# host.net
KiCad netlist of a schematic drawn in EAGLE
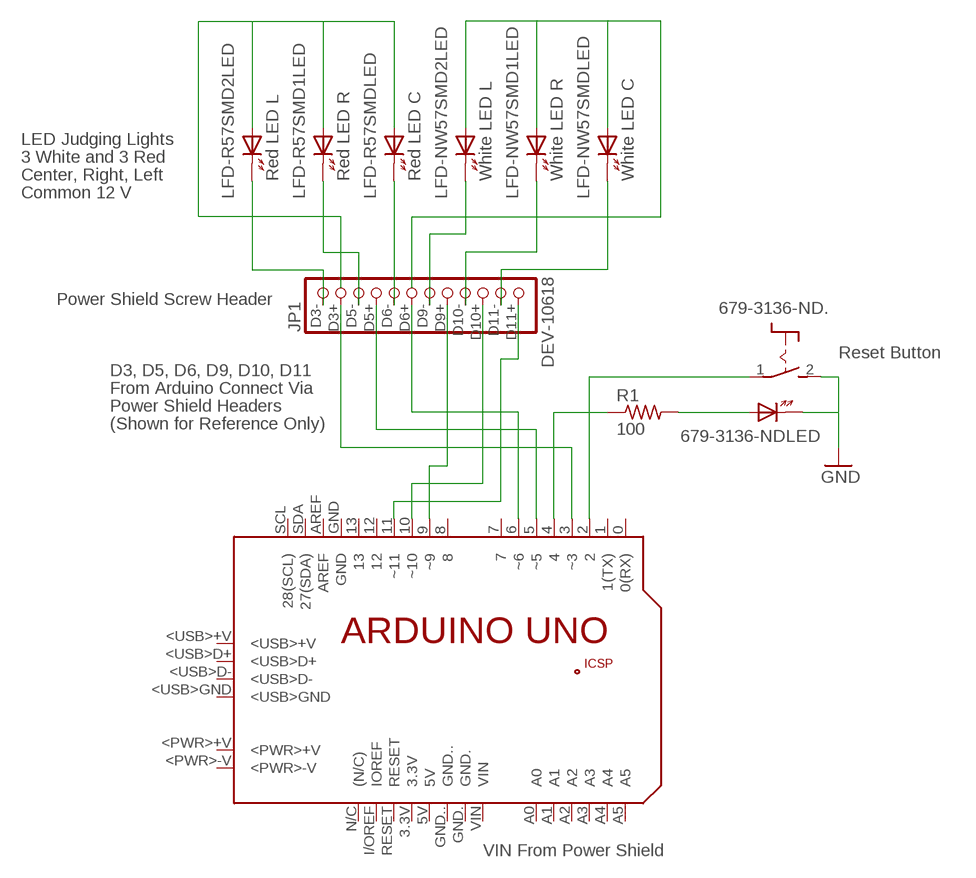
[diagram p0: schematic, sheet 1]

(export (version "E")
  (design (tool "Eeschema 10.0.6"))
  (components
    (comp (ref "679-3136-ND")
      (value "MARQ6425")
      (footprint "eagle-import:MARQ6425")
      (libsource (lib "eagle-import") (part "MARQ6425"))
    )
    (comp (ref "JP1")
      (value "DEV-10618")
      (footprint "eagle-import:1X12")
      (libsource (lib "eagle-import") (part "PINHD-1X12"))
    )
    (comp (ref "LFD-NW57SMD")
      (value "White LED C")
      (footprint "eagle-import:MARQ6425")
      (libsource (lib "eagle-import") (part "MARQ6425"))
    )
    (comp (ref "LFD-NW57SMD1")
      (value "White LED R")
      (footprint "eagle-import:MARQ6425")
      (libsource (lib "eagle-import") (part "MARQ6425"))
    )
    (comp (ref "LFD-NW57SMD2")
      (value "White LED L")
      (footprint "eagle-import:MARQ6425")
      (libsource (lib "eagle-import") (part "MARQ6425"))
    )
    (comp (ref "LFD-R57SMD")
      (value "Red LED C")
      (footprint "eagle-import:MARQ6425")
      (libsource (lib "eagle-import") (part "MARQ6425"))
    )
    (comp (ref "LFD-R57SMD1")
      (value "Red LED R")
      (footprint "eagle-import:MARQ6425")
      (libsource (lib "eagle-import") (part "MARQ6425"))
    )
    (comp (ref "LFD-R57SMD2")
      (value "Red LED L")
      (footprint "eagle-import:MARQ6425")
      (libsource (lib "eagle-import") (part "MARQ6425"))
    )
    (comp (ref "PCB1")
      (value "ARDUINO_UNO")
      (footprint "eagle-import:ARDUINO_UNO")
      (libsource (lib "eagle-import") (part "ARDUINO_UNO"))
    )
    (comp (ref "R1")
      (value "100")
      (footprint "eagle-import:0204V")
      (libsource (lib "eagle-import") (part "R-US_0204/2V"))
    )
  )
  (nets
    (net (code "1") (name "GND") (class "Default")
      (node (ref "679-3136-ND") (pin "2") (pinfunction "S_2") (pintype "passive"))
      (node (ref "679-3136-ND") (pin "K") (pinfunction "K_K") (pintype "passive"))
    )
    (net (code "2") (name "Net-(679-3136-ND-PadA)") (class "Default")
      (node (ref "679-3136-ND") (pin "A") (pinfunction "A_A") (pintype "passive"))
      (node (ref "R1") (pin "2") (pinfunction "2_2") (pintype "passive"))
    )
    (net (code "3") (name "Net-(679-3136-NDA-P)") (class "Default")
      (node (ref "679-3136-ND") (pin "1") (pinfunction "P_1") (pintype "passive"))
      (node (ref "PCB1") (pin "2") (pinfunction "2_2") (pintype "bidirectional"))
    )
    (net (code "4") (name "Net-(JP1-PadD3-)") (class "Default")
      (node (ref "JP1") (pin "D3-") (pinfunction "D3-_D3-") (pintype "passive"))
      (node (ref "LFD-R57SMD2") (pin "K") (pinfunction "K_K") (pintype "passive"))
    )
    (net (code "5") (name "Net-(JP1-PadD5-)") (class "Default")
      (node (ref "JP1") (pin "D5-") (pinfunction "D5-_D5-") (pintype "passive"))
      (node (ref "LFD-R57SMD1") (pin "K") (pinfunction "K_K") (pintype "passive"))
    )
    (net (code "6") (name "Net-(JP1-PadD6-)") (class "Default")
      (node (ref "JP1") (pin "D6-") (pinfunction "D6-_D6-") (pintype "passive"))
      (node (ref "LFD-R57SMD") (pin "K") (pinfunction "K_K") (pintype "passive"))
    )
    (net (code "7") (name "Net-(JP1-PadD9-)") (class "Default")
      (node (ref "JP1") (pin "D9-") (pinfunction "D9-_D9-") (pintype "passive"))
      (node (ref "LFD-NW57SMD2") (pin "K") (pinfunction "K_K") (pintype "passive"))
    )
    (net (code "8") (name "Net-(JP1-PadD10-)") (class "Default")
      (node (ref "JP1") (pin "D10-") (pinfunction "D10-_D10-") (pintype "passive"))
      (node (ref "LFD-NW57SMD1") (pin "K") (pinfunction "K_K") (pintype "passive"))
    )
    (net (code "9") (name "Net-(JP1-PadD11-)") (class "Default")
      (node (ref "JP1") (pin "D11-") (pinfunction "D11-_D11-") (pintype "passive"))
      (node (ref "LFD-NW57SMD") (pin "K") (pinfunction "K_K") (pintype "passive"))
    )
    (net (code "10") (name "Net-(LFD-NW57SMD-PadA)") (class "Default")
      (node (ref "LFD-NW57SMD") (pin "A") (pinfunction "A_A") (pintype "passive"))
      (node (ref "LFD-NW57SMD1") (pin "A") (pinfunction "A_A") (pintype "passive"))
      (node (ref "LFD-NW57SMD2") (pin "A") (pinfunction "A_A") (pintype "passive"))
    )
    (net (code "11") (name "Net-(LFD-R57SMD-PadA)") (class "Default")
      (node (ref "LFD-R57SMD") (pin "A") (pinfunction "A_A") (pintype "passive"))
      (node (ref "LFD-R57SMD1") (pin "A") (pinfunction "A_A") (pintype "passive"))
      (node (ref "LFD-R57SMD2") (pin "A") (pinfunction "A_A") (pintype "passive"))
    )
    (net (code "12") (name "Net-(PCB1-Pad4)") (class "Default")
      (node (ref "PCB1") (pin "4") (pinfunction "4_4") (pintype "bidirectional"))
      (node (ref "R1") (pin "1") (pinfunction "1_1") (pintype "passive"))
    )
    (net (code "13") (name "Net-(PCB1-~{3})") (class "Default")
      (node (ref "JP1") (pin "D3+") (pinfunction "D3+_D3+") (pintype "passive"))
      (node (ref "PCB1") (pin "3") (pinfunction "~{3}_3") (pintype "bidirectional"))
    )
    (net (code "14") (name "Net-(PCB1-~{5})") (class "Default")
      (node (ref "JP1") (pin "D5+") (pinfunction "D5+_D5+") (pintype "passive"))
      (node (ref "PCB1") (pin "5") (pinfunction "~{5}_5") (pintype "bidirectional"))
    )
    (net (code "15") (name "Net-(PCB1-~{6})") (class "Default")
      (node (ref "JP1") (pin "D6+") (pinfunction "D6+_D6+") (pintype "passive"))
      (node (ref "PCB1") (pin "6") (pinfunction "~{6}_6") (pintype "bidirectional"))
    )
    (net (code "16") (name "Net-(PCB1-~{9})") (class "Default")
      (node (ref "JP1") (pin "D9+") (pinfunction "D9+_D9+") (pintype "passive"))
      (node (ref "PCB1") (pin "9") (pinfunction "~{9}_9") (pintype "bidirectional"))
    )
    (net (code "17") (name "Net-(PCB1-~{10})") (class "Default")
      (node (ref "JP1") (pin "D10+") (pinfunction "D10+_D10+") (pintype "passive"))
      (node (ref "PCB1") (pin "10") (pinfunction "~{10}_10") (pintype "bidirectional"))
    )
    (net (code "18") (name "Net-(PCB1-~{11})") (class "Default")
      (node (ref "JP1") (pin "D11+") (pinfunction "D11+_D11+") (pintype "passive"))
      (node (ref "PCB1") (pin "11") (pinfunction "~{11}_11") (pintype "bidirectional"))
    )
    (net (code "19") (name "unconnected-(PCB1-(N{slash}C)-PadN{slash}C)") (class "Default")
      (node (ref "PCB1") (pin "N/C") (pinfunction "(N/C)_N/C") (pintype "bidirectional"))
    )
    (net (code "20") (name "unconnected-(PCB1-0(RX)-Pad0)") (class "Default")
      (node (ref "PCB1") (pin "0") (pinfunction "0(RX)_0") (pintype "bidirectional"))
    )
    (net (code "21") (name "unconnected-(PCB1-1(TX)-Pad1)") (class "Default")
      (node (ref "PCB1") (pin "1") (pinfunction "1(TX)_1") (pintype "bidirectional"))
    )
    (net (code "22") (name "unconnected-(PCB1-27(SDA)-PadSDA)") (class "Default")
      (node (ref "PCB1") (pin "SDA") (pinfunction "27(SDA)_SDA") (pintype "bidirectional"))
    )
    (net (code "23") (name "unconnected-(PCB1-28(SCL)-PadSCL)") (class "Default")
      (node (ref "PCB1") (pin "SCL") (pinfunction "28(SCL)_SCL") (pintype "bidirectional"))
    )
    (net (code "24") (name "unconnected-(PCB1-IOREF-PadI{slash}OREF)") (class "Default")
      (node (ref "PCB1") (pin "I/OREF") (pinfunction "IOREF_I/OREF") (pintype "bidirectional"))
    )
    (net (code "25") (name "unconnected-(PCB1-Pad+5V)") (class "Default")
      (node (ref "PCB1") (pin "+5V") (pinfunction "+5V_+5V") (pintype "bidirectional"))
    )
    (net (code "26") (name "unconnected-(PCB1-Pad3.3V)") (class "Default")
      (node (ref "PCB1") (pin "3.3V") (pinfunction "3.3V_3.3V") (pintype "bidirectional"))
    )
    (net (code "27") (name "unconnected-(PCB1-Pad5V)") (class "Default")
      (node (ref "PCB1") (pin "5V") (pinfunction "5V_5V") (pintype "bidirectional"))
    )
    (net (code "28") (name "unconnected-(PCB1-Pad7)") (class "Default")
      (node (ref "PCB1") (pin "7") (pinfunction "7_7") (pintype "bidirectional"))
    )
    (net (code "29") (name "unconnected-(PCB1-Pad8)") (class "Default")
      (node (ref "PCB1") (pin "8") (pinfunction "8_8") (pintype "bidirectional"))
    )
    (net (code "30") (name "unconnected-(PCB1-Pad12)") (class "Default")
      (node (ref "PCB1") (pin "12") (pinfunction "12_12") (pintype "bidirectional"))
    )
    (net (code "31") (name "unconnected-(PCB1-Pad13)") (class "Default")
      (node (ref "PCB1") (pin "13") (pinfunction "13_13") (pintype "bidirectional"))
    )
    (net (code "32") (name "unconnected-(PCB1-Pad<PWR>+V)") (class "Default")
      (node (ref "PCB1") (pin "<PWR>+V") (pinfunction "<PWR>+V_<PWR>+V") (pintype "bidirectional"))
    )
    (net (code "33") (name "unconnected-(PCB1-Pad<PWR>-V)") (class "Default")
      (node (ref "PCB1") (pin "<PWR>-V") (pinfunction "<PWR>-V_<PWR>-V") (pintype "bidirectional"))
    )
    (net (code "34") (name "unconnected-(PCB1-Pad<USB>+V)") (class "Default")
      (node (ref "PCB1") (pin "<USB>+V") (pinfunction "<USB>+V_<USB>+V") (pintype "bidirectional"))
    )
    (net (code "35") (name "unconnected-(PCB1-Pad<USB>D+)") (class "Default")
      (node (ref "PCB1") (pin "<USB>D+") (pinfunction "<USB>D+_<USB>D+") (pintype "bidirectional"))
    )
    (net (code "36") (name "unconnected-(PCB1-Pad<USB>D-)") (class "Default")
      (node (ref "PCB1") (pin "<USB>D-") (pinfunction "<USB>D-_<USB>D-") (pintype "bidirectional"))
    )
    (net (code "37") (name "unconnected-(PCB1-Pad<USB>GND)") (class "Default")
      (node (ref "PCB1") (pin "<USB>GND") (pinfunction "<USB>GND_<USB>GND") (pintype "bidirectional"))
    )
    (net (code "38") (name "unconnected-(PCB1-PadA0)") (class "Default")
      (node (ref "PCB1") (pin "A0") (pinfunction "A0_A0") (pintype "bidirectional"))
    )
    (net (code "39") (name "unconnected-(PCB1-PadA1)") (class "Default")
      (node (ref "PCB1") (pin "A1") (pinfunction "A1_A1") (pintype "bidirectional"))
    )
    (net (code "40") (name "unconnected-(PCB1-PadA2)") (class "Default")
      (node (ref "PCB1") (pin "A2") (pinfunction "A2_A2") (pintype "bidirectional"))
    )
    (net (code "41") (name "unconnected-(PCB1-PadA3)") (class "Default")
      (node (ref "PCB1") (pin "A3") (pinfunction "A3_A3") (pintype "bidirectional"))
    )
    (net (code "42") (name "unconnected-(PCB1-PadA4)") (class "Default")
      (node (ref "PCB1") (pin "A4") (pinfunction "A4_A4") (pintype "bidirectional"))
    )
    (net (code "43") (name "unconnected-(PCB1-PadA5)") (class "Default")
      (node (ref "PCB1") (pin "A5") (pinfunction "A5_A5") (pintype "bidirectional"))
    )
    (net (code "44") (name "unconnected-(PCB1-PadAREF)") (class "Default")
      (node (ref "PCB1") (pin "AREF") (pinfunction "AREF_AREF") (pintype "bidirectional"))
    )
    (net (code "45") (name "unconnected-(PCB1-PadGND)") (class "Default")
      (node (ref "PCB1") (pin "GND") (pinfunction "GND_GND") (pintype "bidirectional"))
    )
    (net (code "46") (name "unconnected-(PCB1-PadGND.)") (class "Default")
      (node (ref "PCB1") (pin "GND.") (pinfunction "GND._GND.") (pintype "bidirectional"))
    )
    (net (code "47") (name "unconnected-(PCB1-PadGND..)") (class "Default")
      (node (ref "PCB1") (pin "GND..") (pinfunction "GND.._GND..") (pintype "bidirectional"))
    )
    (net (code "48") (name "unconnected-(PCB1-PadGND_)") (class "Default")
      (node (ref "PCB1") (pin "GND_") (pinfunction "GND__GND_") (pintype "bidirectional"))
    )
    (net (code "49") (name "unconnected-(PCB1-PadMISO)") (class "Default")
      (node (ref "PCB1") (pin "MISO") (pinfunction "MISO_MISO") (pintype "bidirectional"))
    )
    (net (code "50") (name "unconnected-(PCB1-PadMOSI)") (class "Default")
      (node (ref "PCB1") (pin "MOSI") (pinfunction "MOSI_MOSI") (pintype "bidirectional"))
    )
    (net (code "51") (name "unconnected-(PCB1-PadRESET)") (class "Default")
      (node (ref "PCB1") (pin "RESET") (pinfunction "RESET_RESET") (pintype "bidirectional"))
    )
    (net (code "52") (name "unconnected-(PCB1-PadRESET.)") (class "Default")
      (node (ref "PCB1") (pin "RESET.") (pinfunction "RESET._RESET.") (pintype "bidirectional"))
    )
    (net (code "53") (name "unconnected-(PCB1-PadSCK)") (class "Default")
      (node (ref "PCB1") (pin "SCK") (pinfunction "SCK_SCK") (pintype "bidirectional"))
    )
    (net (code "54") (name "unconnected-(PCB1-PadVIN)") (class "Default")
      (node (ref "PCB1") (pin "VIN") (pinfunction "VIN_VIN") (pintype "bidirectional"))
    )
  )
)
